# OSV-UserInterface.net
KiCad netlist of a schematic drawn in Altium Designer
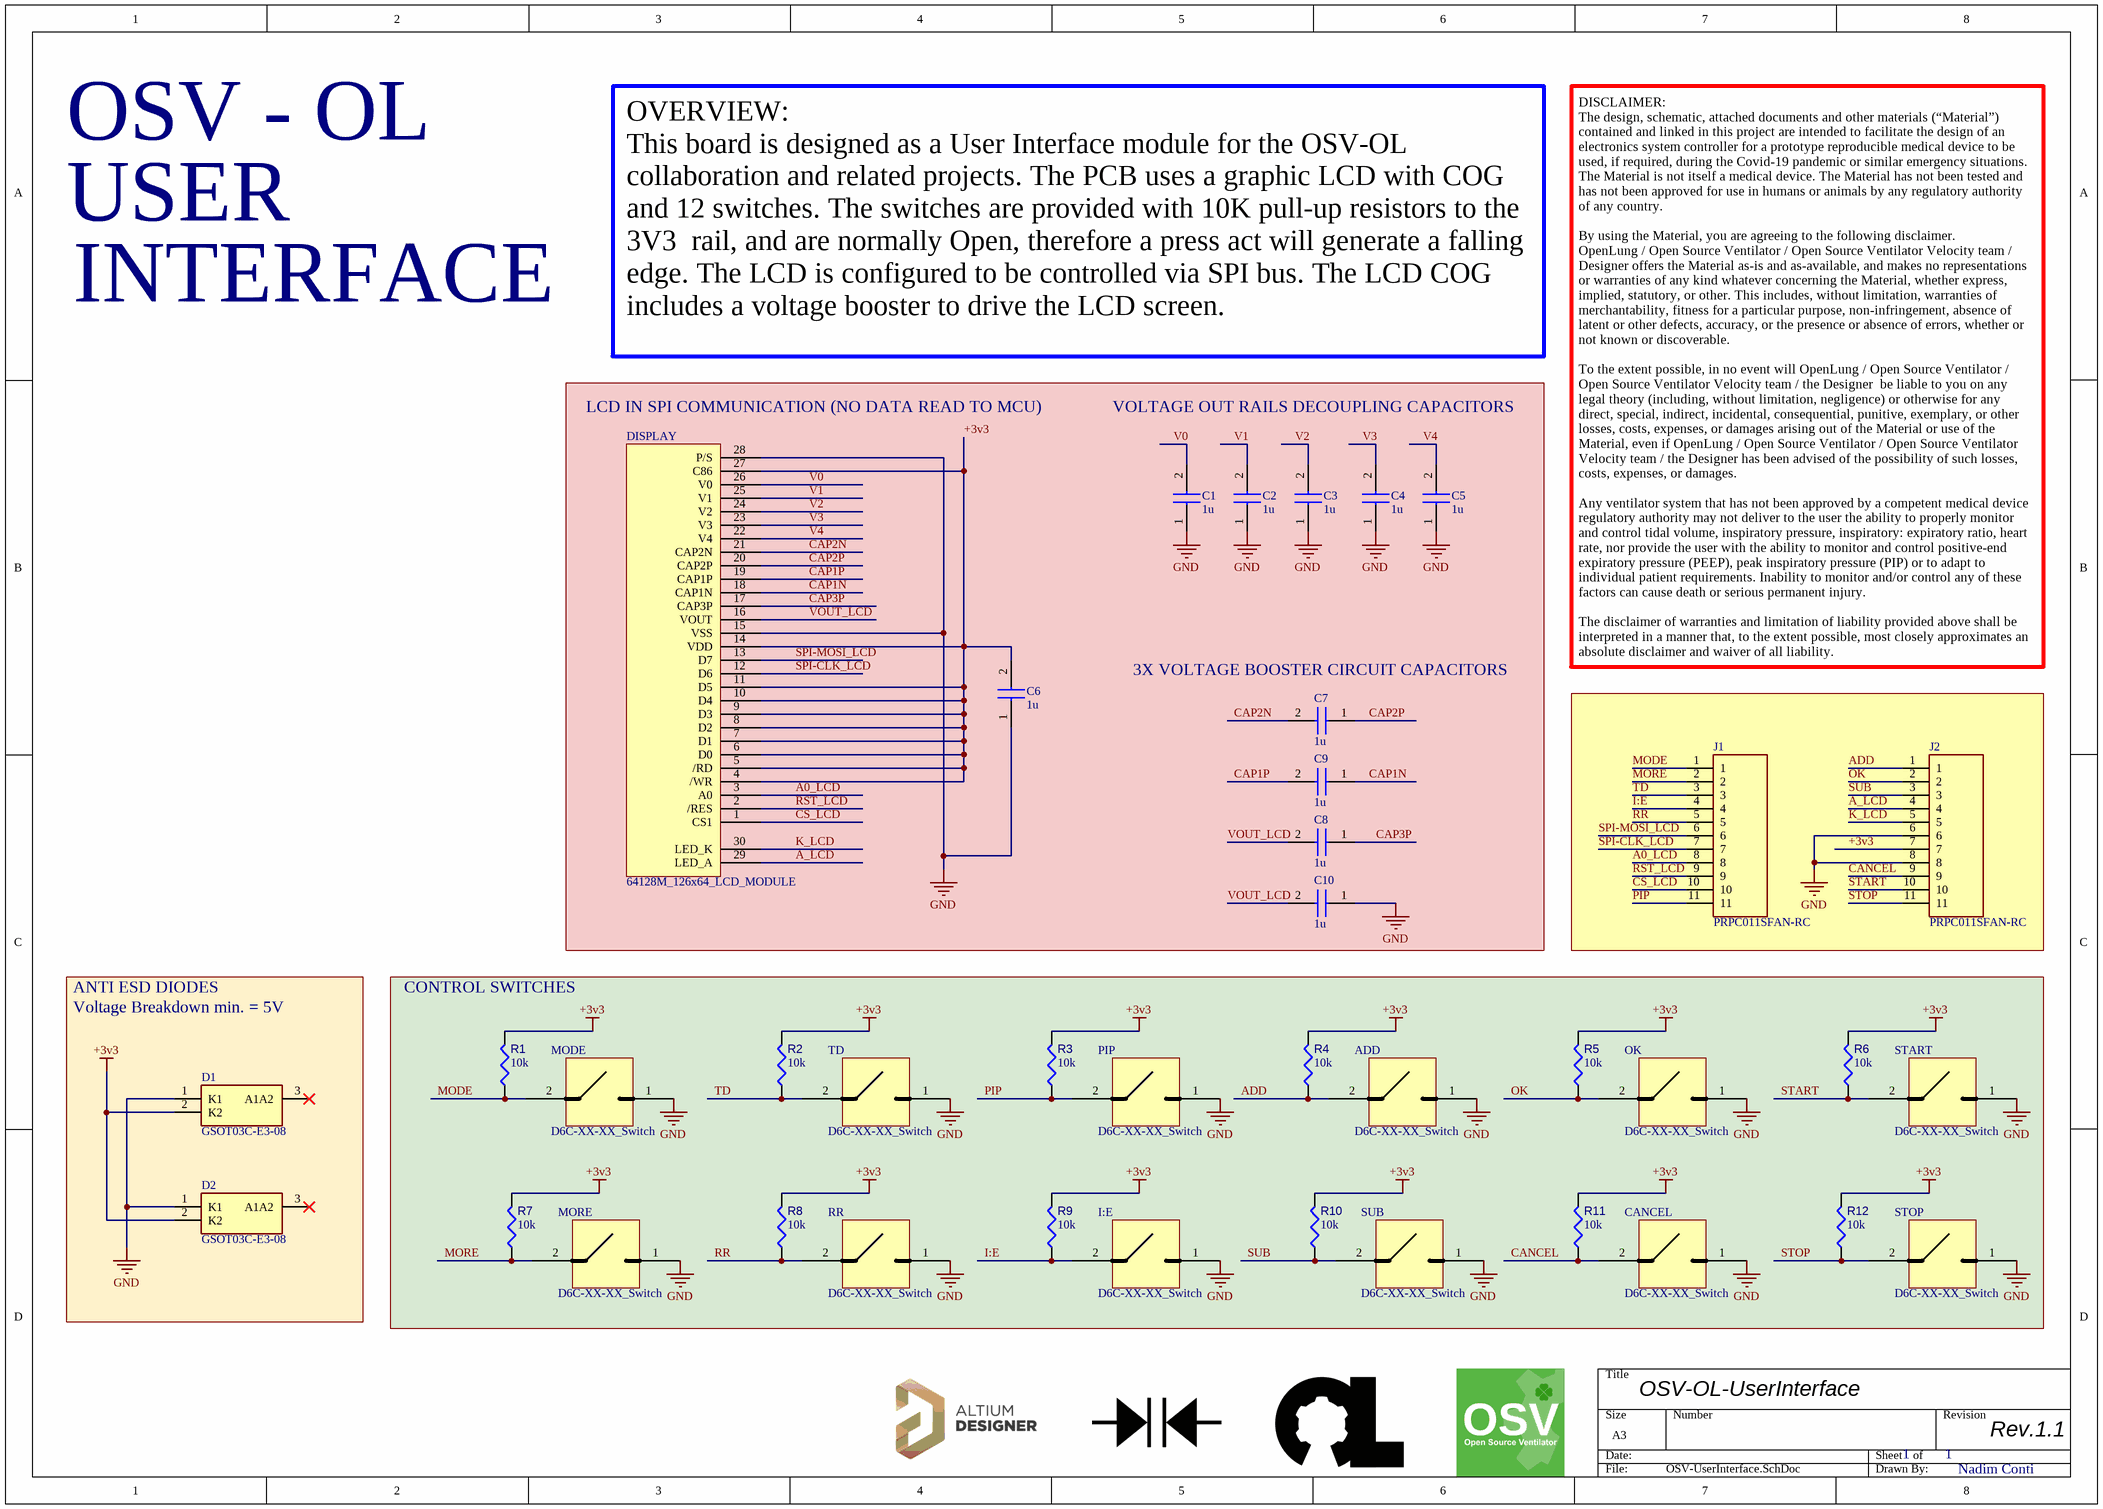
[diagram p0: OSV-UserInterface.SchDoc]

(export (version "E")
  (design (tool "Eeschema 10.0.6"))
  (components
    (comp (ref "ADD")
      (value "D6C-XX-XX_Switch")
      (footprint "D6C-60-F1_Blue-Switch")
      (libsource (lib "64128M_lcd") (part "D6C-XX-XX_Switch"))
    )
    (comp (ref "C1")
      (value "GCM21BR71H105KA03K")
      (footprint "SamacSys:CAPC2012X140N")
      (description "Capacitor")
      (fields (field (name "MOUSER PART NUMBER") "81-GCM21BR71H105KA3K") (field (name "CAPACITANCE") "1u"))
      (libsource (lib "*") (part "GCM21BR71H105KA03K"))
    )
    (comp (ref "C2")
      (value "GCM21BR71H105KA03K")
      (footprint "SamacSys:CAPC2012X140N")
      (description "Capacitor")
      (fields (field (name "MOUSER PART NUMBER") "81-GCM21BR71H105KA3K") (field (name "CAPACITANCE") "1u"))
      (libsource (lib "*") (part "GCM21BR71H105KA03K"))
    )
    (comp (ref "C3")
      (value "GCM21BR71H105KA03K")
      (footprint "SamacSys:CAPC2012X140N")
      (description "Capacitor")
      (fields (field (name "MOUSER PART NUMBER") "81-GCM21BR71H105KA3K") (field (name "CAPACITANCE") "1u"))
      (libsource (lib "*") (part "GCM21BR71H105KA03K"))
    )
    (comp (ref "C4")
      (value "GCM21BR71H105KA03K")
      (footprint "SamacSys:CAPC2012X140N")
      (description "Capacitor")
      (fields (field (name "MOUSER PART NUMBER") "81-GCM21BR71H105KA3K") (field (name "CAPACITANCE") "1u"))
      (libsource (lib "*") (part "GCM21BR71H105KA03K"))
    )
    (comp (ref "C5")
      (value "GCM21BR71H105KA03K")
      (footprint "SamacSys:CAPC2012X140N")
      (description "Capacitor")
      (fields (field (name "MOUSER PART NUMBER") "81-GCM21BR71H105KA3K") (field (name "CAPACITANCE") "1u"))
      (libsource (lib "*") (part "GCM21BR71H105KA03K"))
    )
    (comp (ref "C6")
      (value "GCM21BR71H105KA03K")
      (footprint "SamacSys:CAPC2012X140N")
      (description "Capacitor")
      (fields (field (name "MOUSER PART NUMBER") "81-GCM21BR71H105KA3K") (field (name "CAPACITANCE") "1u"))
      (libsource (lib "*") (part "GCM21BR71H105KA03K"))
    )
    (comp (ref "C7")
      (value "GCM21BR71H105KA03K")
      (footprint "SamacSys:CAPC2012X140N")
      (description "Capacitor")
      (fields (field (name "MOUSER PART NUMBER") "81-GCM21BR71H105KA3K") (field (name "CAPACITANCE") "1u"))
      (libsource (lib "*") (part "GCM21BR71H105KA03K"))
    )
    (comp (ref "C8")
      (value "GCM21BR71H105KA03K")
      (footprint "SamacSys:CAPC2012X140N")
      (description "Capacitor")
      (fields (field (name "MOUSER PART NUMBER") "81-GCM21BR71H105KA3K") (field (name "CAPACITANCE") "1u"))
      (libsource (lib "*") (part "GCM21BR71H105KA03K"))
    )
    (comp (ref "C9")
      (value "GCM21BR71H105KA03K")
      (footprint "SamacSys:CAPC2012X140N")
      (description "Capacitor")
      (fields (field (name "MOUSER PART NUMBER") "81-GCM21BR71H105KA3K") (field (name "CAPACITANCE") "1u"))
      (libsource (lib "*") (part "GCM21BR71H105KA03K"))
    )
    (comp (ref "C10")
      (value "GCM21BR71H105KA03K")
      (footprint "SamacSys:CAPC2012X140N")
      (description "Capacitor")
      (fields (field (name "MOUSER PART NUMBER") "81-GCM21BR71H105KA3K") (field (name "CAPACITANCE") "1u"))
      (libsource (lib "*") (part "GCM21BR71H105KA03K"))
    )
    (comp (ref "CANCEL")
      (value "D6C-XX-XX_Switch")
      (footprint "D6C-30-F1_YELLOW-SWITCH")
      (libsource (lib "64128M_lcd") (part "D6C-XX-XX_Switch"))
    )
    (comp (ref "D1")
      (value "GSOT03C-E3-08")
      (footprint "SamacSys:SOT95P248X115-3N")
      (description "Diode")
      (fields
        (field (name "MOUSER PART NUMBER") "78-GSOT03C-E3-08")
        (field (name "RS PART NUMBER") "6997957P")
      )
      (libsource (lib "*") (part "GSOT03C-E3-08"))
    )
    (comp (ref "D2")
      (value "GSOT03C-E3-08")
      (footprint "SamacSys:SOT95P248X115-3N")
      (description "Diode")
      (fields
        (field (name "MOUSER PART NUMBER") "78-GSOT03C-E3-08")
        (field (name "RS PART NUMBER") "6997957P")
      )
      (libsource (lib "*") (part "GSOT03C-E3-08"))
    )
    (comp (ref "DISPLAY")
      (value "64128M_126x64_LCD_MODULE")
      (footprint "64128M_LCD")
      (description "64128M Series LCD Module (128 x 64 DOTS)")
      (libsource (lib "64128M_lcd") (part "64128M_126x64_LCD_MODULE"))
    )
    (comp (ref "I:E")
      (value "D6C-XX-XX_Switch")
      (footprint "D6C-00-F1_White-Switch")
      (libsource (lib "64128M_lcd") (part "D6C-XX-XX_Switch"))
    )
    (comp (ref "J1")
      (value "PRPC011SFAN-RC")
      (footprint "SamacSys:HDRV11W64P254_1X11_2794X254X1058P")
      (description "Connector")
      (libsource (lib "*") (part "PRPC011SFAN-RC"))
    )
    (comp (ref "J2")
      (value "PRPC011SFAN-RC")
      (footprint "SamacSys:HDRV11W64P254_1X11_2794X254X1058P")
      (description "Connector")
      (libsource (lib "*") (part "PRPC011SFAN-RC"))
    )
    (comp (ref "MODE")
      (value "D6C-XX-XX_Switch")
      (footprint "D6C-30-F1_YELLOW-SWITCH")
      (libsource (lib "64128M_lcd") (part "D6C-XX-XX_Switch"))
    )
    (comp (ref "MORE")
      (value "D6C-XX-XX_Switch")
      (footprint "D6C-00-F1_White-Switch")
      (libsource (lib "64128M_lcd") (part "D6C-XX-XX_Switch"))
    )
    (comp (ref "OK")
      (value "D6C-XX-XX_Switch")
      (footprint "D6C-50-F1_GREEN-Switch")
      (libsource (lib "64128M_lcd") (part "D6C-XX-XX_Switch"))
    )
    (comp (ref "PIP")
      (value "D6C-XX-XX_Switch")
      (footprint "D6C-00-F1_White-Switch")
      (libsource (lib "64128M_lcd") (part "D6C-XX-XX_Switch"))
    )
    (comp (ref "R1")
      (value "10k")
      (footprint "RESC2013X50X35ML15T15")
      (description "Chip Resistor, 10 KOhm, +/- 1%, 125 mW, -55 to 155 degC, 0805 (2012 Metric)")
      (fields (field (name "POWER") "125mW") (field (name "TOLERANCE") "1%"))
      (libsource (lib "Altium Concord Pro on A365") (part "RES-2"))
    )
    (comp (ref "R2")
      (value "10k")
      (footprint "RESC2013X50X35ML15T15")
      (description "Chip Resistor, 10 KOhm, +/- 1%, 125 mW, -55 to 155 degC, 0805 (2012 Metric)")
      (fields (field (name "POWER") "125mW") (field (name "TOLERANCE") "1%"))
      (libsource (lib "Altium Concord Pro on A365") (part "RES-2"))
    )
    (comp (ref "R3")
      (value "10k")
      (footprint "RESC2013X50X35ML15T15")
      (description "Chip Resistor, 10 KOhm, +/- 1%, 125 mW, -55 to 155 degC, 0805 (2012 Metric)")
      (fields (field (name "POWER") "125mW") (field (name "TOLERANCE") "1%"))
      (libsource (lib "Altium Concord Pro on A365") (part "RES-2"))
    )
    (comp (ref "R4")
      (value "10k")
      (footprint "RESC2013X50X35ML15T15")
      (description "Chip Resistor, 10 KOhm, +/- 1%, 125 mW, -55 to 155 degC, 0805 (2012 Metric)")
      (fields (field (name "POWER") "125mW") (field (name "TOLERANCE") "1%"))
      (libsource (lib "Altium Concord Pro on A365") (part "RES-2"))
    )
    (comp (ref "R5")
      (value "10k")
      (footprint "RESC2013X50X35ML15T15")
      (description "Chip Resistor, 10 KOhm, +/- 1%, 125 mW, -55 to 155 degC, 0805 (2012 Metric)")
      (fields (field (name "POWER") "125mW") (field (name "TOLERANCE") "1%"))
      (libsource (lib "Altium Concord Pro on A365") (part "RES-2"))
    )
    (comp (ref "R6")
      (value "10k")
      (footprint "RESC2013X50X35ML15T15")
      (description "Chip Resistor, 10 KOhm, +/- 1%, 125 mW, -55 to 155 degC, 0805 (2012 Metric)")
      (fields (field (name "POWER") "125mW") (field (name "TOLERANCE") "1%"))
      (libsource (lib "Altium Concord Pro on A365") (part "RES-2"))
    )
    (comp (ref "R7")
      (value "10k")
      (footprint "RESC2013X50X35ML15T15")
      (description "Chip Resistor, 10 KOhm, +/- 1%, 125 mW, -55 to 155 degC, 0805 (2012 Metric)")
      (fields (field (name "POWER") "125mW") (field (name "TOLERANCE") "1%"))
      (libsource (lib "Altium Concord Pro on A365") (part "RES-2"))
    )
    (comp (ref "R8")
      (value "10k")
      (footprint "RESC2013X50X35ML15T15")
      (description "Chip Resistor, 10 KOhm, +/- 1%, 125 mW, -55 to 155 degC, 0805 (2012 Metric)")
      (fields (field (name "POWER") "125mW") (field (name "TOLERANCE") "1%"))
      (libsource (lib "Altium Concord Pro on A365") (part "RES-2"))
    )
    (comp (ref "R9")
      (value "10k")
      (footprint "RESC2013X50X35ML15T15")
      (description "Chip Resistor, 10 KOhm, +/- 1%, 125 mW, -55 to 155 degC, 0805 (2012 Metric)")
      (fields (field (name "POWER") "125mW") (field (name "TOLERANCE") "1%"))
      (libsource (lib "Altium Concord Pro on A365") (part "RES-2"))
    )
    (comp (ref "R10")
      (value "10k")
      (footprint "RESC2013X50X35ML15T15")
      (description "Chip Resistor, 10 KOhm, +/- 1%, 125 mW, -55 to 155 degC, 0805 (2012 Metric)")
      (fields (field (name "POWER") "125mW") (field (name "TOLERANCE") "1%"))
      (libsource (lib "Altium Concord Pro on A365") (part "RES-2"))
    )
    (comp (ref "R11")
      (value "10k")
      (footprint "RESC2013X50X35ML15T15")
      (description "Chip Resistor, 10 KOhm, +/- 1%, 125 mW, -55 to 155 degC, 0805 (2012 Metric)")
      (fields (field (name "POWER") "125mW") (field (name "TOLERANCE") "1%"))
      (libsource (lib "Altium Concord Pro on A365") (part "RES-2"))
    )
    (comp (ref "R12")
      (value "10k")
      (footprint "RESC2013X50X35ML15T15")
      (description "Chip Resistor, 10 KOhm, +/- 1%, 125 mW, -55 to 155 degC, 0805 (2012 Metric)")
      (fields (field (name "POWER") "125mW") (field (name "TOLERANCE") "1%"))
      (libsource (lib "Altium Concord Pro on A365") (part "RES-2"))
    )
    (comp (ref "RR")
      (value "D6C-XX-XX_Switch")
      (footprint "D6C-00-F1_White-Switch")
      (libsource (lib "64128M_lcd") (part "D6C-XX-XX_Switch"))
    )
    (comp (ref "START")
      (value "D6C-XX-XX_Switch")
      (footprint "D6C-50-F1_GREEN-Switch")
      (libsource (lib "64128M_lcd") (part "D6C-XX-XX_Switch"))
    )
    (comp (ref "STOP")
      (value "D6C-XX-XX_Switch")
      (footprint "D6C-40-F1_RED-SWITCH")
      (libsource (lib "64128M_lcd") (part "D6C-XX-XX_Switch"))
    )
    (comp (ref "SUB")
      (value "D6C-XX-XX_Switch")
      (footprint "D6C-60-F1_Blue-Switch")
      (libsource (lib "64128M_lcd") (part "D6C-XX-XX_Switch"))
    )
    (comp (ref "TD")
      (value "D6C-XX-XX_Switch")
      (footprint "D6C-00-F1_White-Switch")
      (libsource (lib "64128M_lcd") (part "D6C-XX-XX_Switch"))
    )
  )
  (nets
    (net (code "1") (name "+3v3") (class "Default")
      (node (ref "C6") (pin "2") (pinfunction "2_2") (pintype "passive"))
      (node (ref "D1") (pin "2") (pinfunction "K2_2") (pintype "passive"))
      (node (ref "D2") (pin "2") (pinfunction "K2_2") (pintype "passive"))
      (node (ref "DISPLAY") (pin "10") (pinfunction "D4_10") (pintype "passive"))
      (node (ref "DISPLAY") (pin "11") (pinfunction "D5_11") (pintype "passive"))
      (node (ref "DISPLAY") (pin "14") (pinfunction "VDD_14") (pintype "passive"))
      (node (ref "DISPLAY") (pin "27") (pinfunction "C86_27") (pintype "passive"))
      (node (ref "DISPLAY") (pin "4") (pinfunction "/WR_4") (pintype "passive"))
      (node (ref "DISPLAY") (pin "5") (pinfunction "/RD_5") (pintype "passive"))
      (node (ref "DISPLAY") (pin "6") (pinfunction "D0_6") (pintype "passive"))
      (node (ref "DISPLAY") (pin "7") (pinfunction "D1_7") (pintype "passive"))
      (node (ref "DISPLAY") (pin "8") (pinfunction "D2_8") (pintype "passive"))
      (node (ref "DISPLAY") (pin "9") (pinfunction "D3_9") (pintype "passive"))
      (node (ref "J2") (pin "7") (pinfunction "7_7") (pintype "passive"))
      (node (ref "R1") (pin "2") (pinfunction "2_2") (pintype "passive"))
      (node (ref "R10") (pin "2") (pinfunction "2_2") (pintype "passive"))
      (node (ref "R11") (pin "2") (pinfunction "2_2") (pintype "passive"))
      (node (ref "R12") (pin "2") (pinfunction "2_2") (pintype "passive"))
      (node (ref "R2") (pin "2") (pinfunction "2_2") (pintype "passive"))
      (node (ref "R3") (pin "2") (pinfunction "2_2") (pintype "passive"))
      (node (ref "R4") (pin "2") (pinfunction "2_2") (pintype "passive"))
      (node (ref "R5") (pin "2") (pinfunction "2_2") (pintype "passive"))
      (node (ref "R6") (pin "2") (pinfunction "2_2") (pintype "passive"))
      (node (ref "R7") (pin "2") (pinfunction "2_2") (pintype "passive"))
      (node (ref "R8") (pin "2") (pinfunction "2_2") (pintype "passive"))
      (node (ref "R9") (pin "2") (pinfunction "2_2") (pintype "passive"))
    )
    (net (code "2") (name "/A0_LCD") (class "Default")
      (node (ref "DISPLAY") (pin "3") (pinfunction "A0_3") (pintype "passive"))
      (node (ref "J1") (pin "8") (pinfunction "8_8") (pintype "passive"))
    )
    (net (code "3") (name "/ADD") (class "Default")
      (node (ref "ADD") (pin "2") (pintype "passive"))
      (node (ref "J2") (pin "1") (pinfunction "1_1") (pintype "passive"))
      (node (ref "R4") (pin "1") (pinfunction "1_1") (pintype "passive"))
    )
    (net (code "4") (name "/A_LCD") (class "Default")
      (node (ref "DISPLAY") (pin "29") (pinfunction "LED_A_29") (pintype "passive"))
      (node (ref "J2") (pin "4") (pinfunction "4_4") (pintype "passive"))
    )
    (net (code "5") (name "/CANCEL") (class "Default")
      (node (ref "CANCEL") (pin "2") (pintype "passive"))
      (node (ref "J2") (pin "9") (pinfunction "9_9") (pintype "passive"))
      (node (ref "R11") (pin "1") (pinfunction "1_1") (pintype "passive"))
    )
    (net (code "6") (name "/CAP1N") (class "Default")
      (node (ref "C9") (pin "1") (pinfunction "1_1") (pintype "passive"))
      (node (ref "DISPLAY") (pin "18") (pinfunction "CAP1N_18") (pintype "passive"))
    )
    (net (code "7") (name "/CAP1P") (class "Default")
      (node (ref "C9") (pin "2") (pinfunction "2_2") (pintype "passive"))
      (node (ref "DISPLAY") (pin "19") (pinfunction "CAP1P_19") (pintype "passive"))
    )
    (net (code "8") (name "/CAP2N") (class "Default")
      (node (ref "C7") (pin "2") (pinfunction "2_2") (pintype "passive"))
      (node (ref "DISPLAY") (pin "21") (pinfunction "CAP2N_21") (pintype "passive"))
    )
    (net (code "9") (name "/CAP2P") (class "Default")
      (node (ref "C7") (pin "1") (pinfunction "1_1") (pintype "passive"))
      (node (ref "DISPLAY") (pin "20") (pinfunction "CAP2P_20") (pintype "passive"))
    )
    (net (code "10") (name "/CAP3P") (class "Default")
      (node (ref "C8") (pin "1") (pinfunction "1_1") (pintype "passive"))
      (node (ref "DISPLAY") (pin "17") (pinfunction "CAP3P_17") (pintype "passive"))
    )
    (net (code "11") (name "/CS_LCD") (class "Default")
      (node (ref "DISPLAY") (pin "1") (pinfunction "CS1_1") (pintype "passive"))
      (node (ref "J1") (pin "10") (pinfunction "10_10") (pintype "passive"))
    )
    (net (code "12") (name "/I:E") (class "Default")
      (node (ref "I:E") (pin "2") (pintype "passive"))
      (node (ref "J1") (pin "4") (pinfunction "4_4") (pintype "passive"))
      (node (ref "R9") (pin "1") (pinfunction "1_1") (pintype "passive"))
    )
    (net (code "13") (name "/K_LCD") (class "Default")
      (node (ref "DISPLAY") (pin "30") (pinfunction "LED_K_30") (pintype "passive"))
      (node (ref "J2") (pin "5") (pinfunction "5_5") (pintype "passive"))
    )
    (net (code "14") (name "/MODE") (class "Default")
      (node (ref "J1") (pin "1") (pinfunction "1_1") (pintype "passive"))
      (node (ref "MODE") (pin "2") (pintype "passive"))
      (node (ref "R1") (pin "1") (pinfunction "1_1") (pintype "passive"))
    )
    (net (code "15") (name "/MORE") (class "Default")
      (node (ref "J1") (pin "2") (pinfunction "2_2") (pintype "passive"))
      (node (ref "MORE") (pin "2") (pintype "passive"))
      (node (ref "R7") (pin "1") (pinfunction "1_1") (pintype "passive"))
    )
    (net (code "16") (name "/OK") (class "Default")
      (node (ref "J2") (pin "2") (pinfunction "2_2") (pintype "passive"))
      (node (ref "OK") (pin "2") (pintype "passive"))
      (node (ref "R5") (pin "1") (pinfunction "1_1") (pintype "passive"))
    )
    (net (code "17") (name "/PIP") (class "Default")
      (node (ref "J1") (pin "11") (pinfunction "11_11") (pintype "passive"))
      (node (ref "PIP") (pin "2") (pintype "passive"))
      (node (ref "R3") (pin "1") (pinfunction "1_1") (pintype "passive"))
    )
    (net (code "18") (name "/RR") (class "Default")
      (node (ref "J1") (pin "5") (pinfunction "5_5") (pintype "passive"))
      (node (ref "R8") (pin "1") (pinfunction "1_1") (pintype "passive"))
      (node (ref "RR") (pin "2") (pintype "passive"))
    )
    (net (code "19") (name "/RST_LCD") (class "Default")
      (node (ref "DISPLAY") (pin "2") (pinfunction "/RES_2") (pintype "passive"))
      (node (ref "J1") (pin "9") (pinfunction "9_9") (pintype "passive"))
    )
    (net (code "20") (name "/SPI-CLK_LCD") (class "Default")
      (node (ref "DISPLAY") (pin "12") (pinfunction "D6_12") (pintype "passive"))
      (node (ref "J1") (pin "7") (pinfunction "7_7") (pintype "passive"))
    )
    (net (code "21") (name "/SPI-MOSI_LCD") (class "Default")
      (node (ref "DISPLAY") (pin "13") (pinfunction "D7_13") (pintype "passive"))
      (node (ref "J1") (pin "6") (pinfunction "6_6") (pintype "passive"))
    )
    (net (code "22") (name "/START") (class "Default")
      (node (ref "J2") (pin "10") (pinfunction "10_10") (pintype "passive"))
      (node (ref "R6") (pin "1") (pinfunction "1_1") (pintype "passive"))
      (node (ref "START") (pin "2") (pintype "passive"))
    )
    (net (code "23") (name "/STOP") (class "Default")
      (node (ref "J2") (pin "11") (pinfunction "11_11") (pintype "passive"))
      (node (ref "R12") (pin "1") (pinfunction "1_1") (pintype "passive"))
      (node (ref "STOP") (pin "2") (pintype "passive"))
    )
    (net (code "24") (name "/SUB") (class "Default")
      (node (ref "J2") (pin "3") (pinfunction "3_3") (pintype "passive"))
      (node (ref "R10") (pin "1") (pinfunction "1_1") (pintype "passive"))
      (node (ref "SUB") (pin "2") (pintype "passive"))
    )
    (net (code "25") (name "/TD") (class "Default")
      (node (ref "J1") (pin "3") (pinfunction "3_3") (pintype "passive"))
      (node (ref "R2") (pin "1") (pinfunction "1_1") (pintype "passive"))
      (node (ref "TD") (pin "2") (pintype "passive"))
    )
    (net (code "26") (name "/V0") (class "Default")
      (node (ref "C1") (pin "2") (pinfunction "2_2") (pintype "passive"))
      (node (ref "DISPLAY") (pin "26") (pinfunction "V0_26") (pintype "passive"))
    )
    (net (code "27") (name "/V1") (class "Default")
      (node (ref "C2") (pin "2") (pinfunction "2_2") (pintype "passive"))
      (node (ref "DISPLAY") (pin "25") (pinfunction "V1_25") (pintype "passive"))
    )
    (net (code "28") (name "/V2") (class "Default")
      (node (ref "C3") (pin "2") (pinfunction "2_2") (pintype "passive"))
      (node (ref "DISPLAY") (pin "24") (pinfunction "V2_24") (pintype "passive"))
    )
    (net (code "29") (name "/V3") (class "Default")
      (node (ref "C4") (pin "2") (pinfunction "2_2") (pintype "passive"))
      (node (ref "DISPLAY") (pin "23") (pinfunction "V3_23") (pintype "passive"))
    )
    (net (code "30") (name "/V4") (class "Default")
      (node (ref "C5") (pin "2") (pinfunction "2_2") (pintype "passive"))
      (node (ref "DISPLAY") (pin "22") (pinfunction "V4_22") (pintype "passive"))
    )
    (net (code "31") (name "/VOUT_LCD") (class "Default")
      (node (ref "C10") (pin "2") (pinfunction "2_2") (pintype "passive"))
      (node (ref "C8") (pin "2") (pinfunction "2_2") (pintype "passive"))
      (node (ref "DISPLAY") (pin "16") (pinfunction "VOUT_16") (pintype "passive"))
    )
    (net (code "32") (name "GND") (class "Default")
      (node (ref "ADD") (pin "1") (pintype "passive"))
      (node (ref "C1") (pin "1") (pinfunction "1_1") (pintype "passive"))
      (node (ref "C10") (pin "1") (pinfunction "1_1") (pintype "passive"))
      (node (ref "C2") (pin "1") (pinfunction "1_1") (pintype "passive"))
      (node (ref "C3") (pin "1") (pinfunction "1_1") (pintype "passive"))
      (node (ref "C4") (pin "1") (pinfunction "1_1") (pintype "passive"))
      (node (ref "C5") (pin "1") (pinfunction "1_1") (pintype "passive"))
      (node (ref "C6") (pin "1") (pinfunction "1_1") (pintype "passive"))
      (node (ref "CANCEL") (pin "1") (pintype "passive"))
      (node (ref "D1") (pin "1") (pinfunction "K1_1") (pintype "passive"))
      (node (ref "D2") (pin "1") (pinfunction "K1_1") (pintype "passive"))
      (node (ref "DISPLAY") (pin "15") (pinfunction "VSS_15") (pintype "passive"))
      (node (ref "DISPLAY") (pin "28") (pinfunction "P/S_28") (pintype "passive"))
      (node (ref "I:E") (pin "1") (pintype "passive"))
      (node (ref "J2") (pin "6") (pinfunction "6_6") (pintype "passive"))
      (node (ref "J2") (pin "8") (pinfunction "8_8") (pintype "passive"))
      (node (ref "MODE") (pin "1") (pintype "passive"))
      (node (ref "MORE") (pin "1") (pintype "passive"))
      (node (ref "OK") (pin "1") (pintype "passive"))
      (node (ref "PIP") (pin "1") (pintype "passive"))
      (node (ref "RR") (pin "1") (pintype "passive"))
      (node (ref "START") (pin "1") (pintype "passive"))
      (node (ref "STOP") (pin "1") (pintype "passive"))
      (node (ref "SUB") (pin "1") (pintype "passive"))
      (node (ref "TD") (pin "1") (pintype "passive"))
    )
    (net (code "33") (name "unconnected-(D1-A1A2-Pad3)") (class "Default")
      (node (ref "D1") (pin "3") (pinfunction "A1A2_3") (pintype "passive+no_connect"))
    )
    (net (code "34") (name "unconnected-(D2-A1A2-Pad3)") (class "Default")
      (node (ref "D2") (pin "3") (pinfunction "A1A2_3") (pintype "passive+no_connect"))
    )
  )
)
